# SCH_Pico_funboard_core2_2026-02-18.net
KiCad netlist of a schematic drawn in EasyEDA
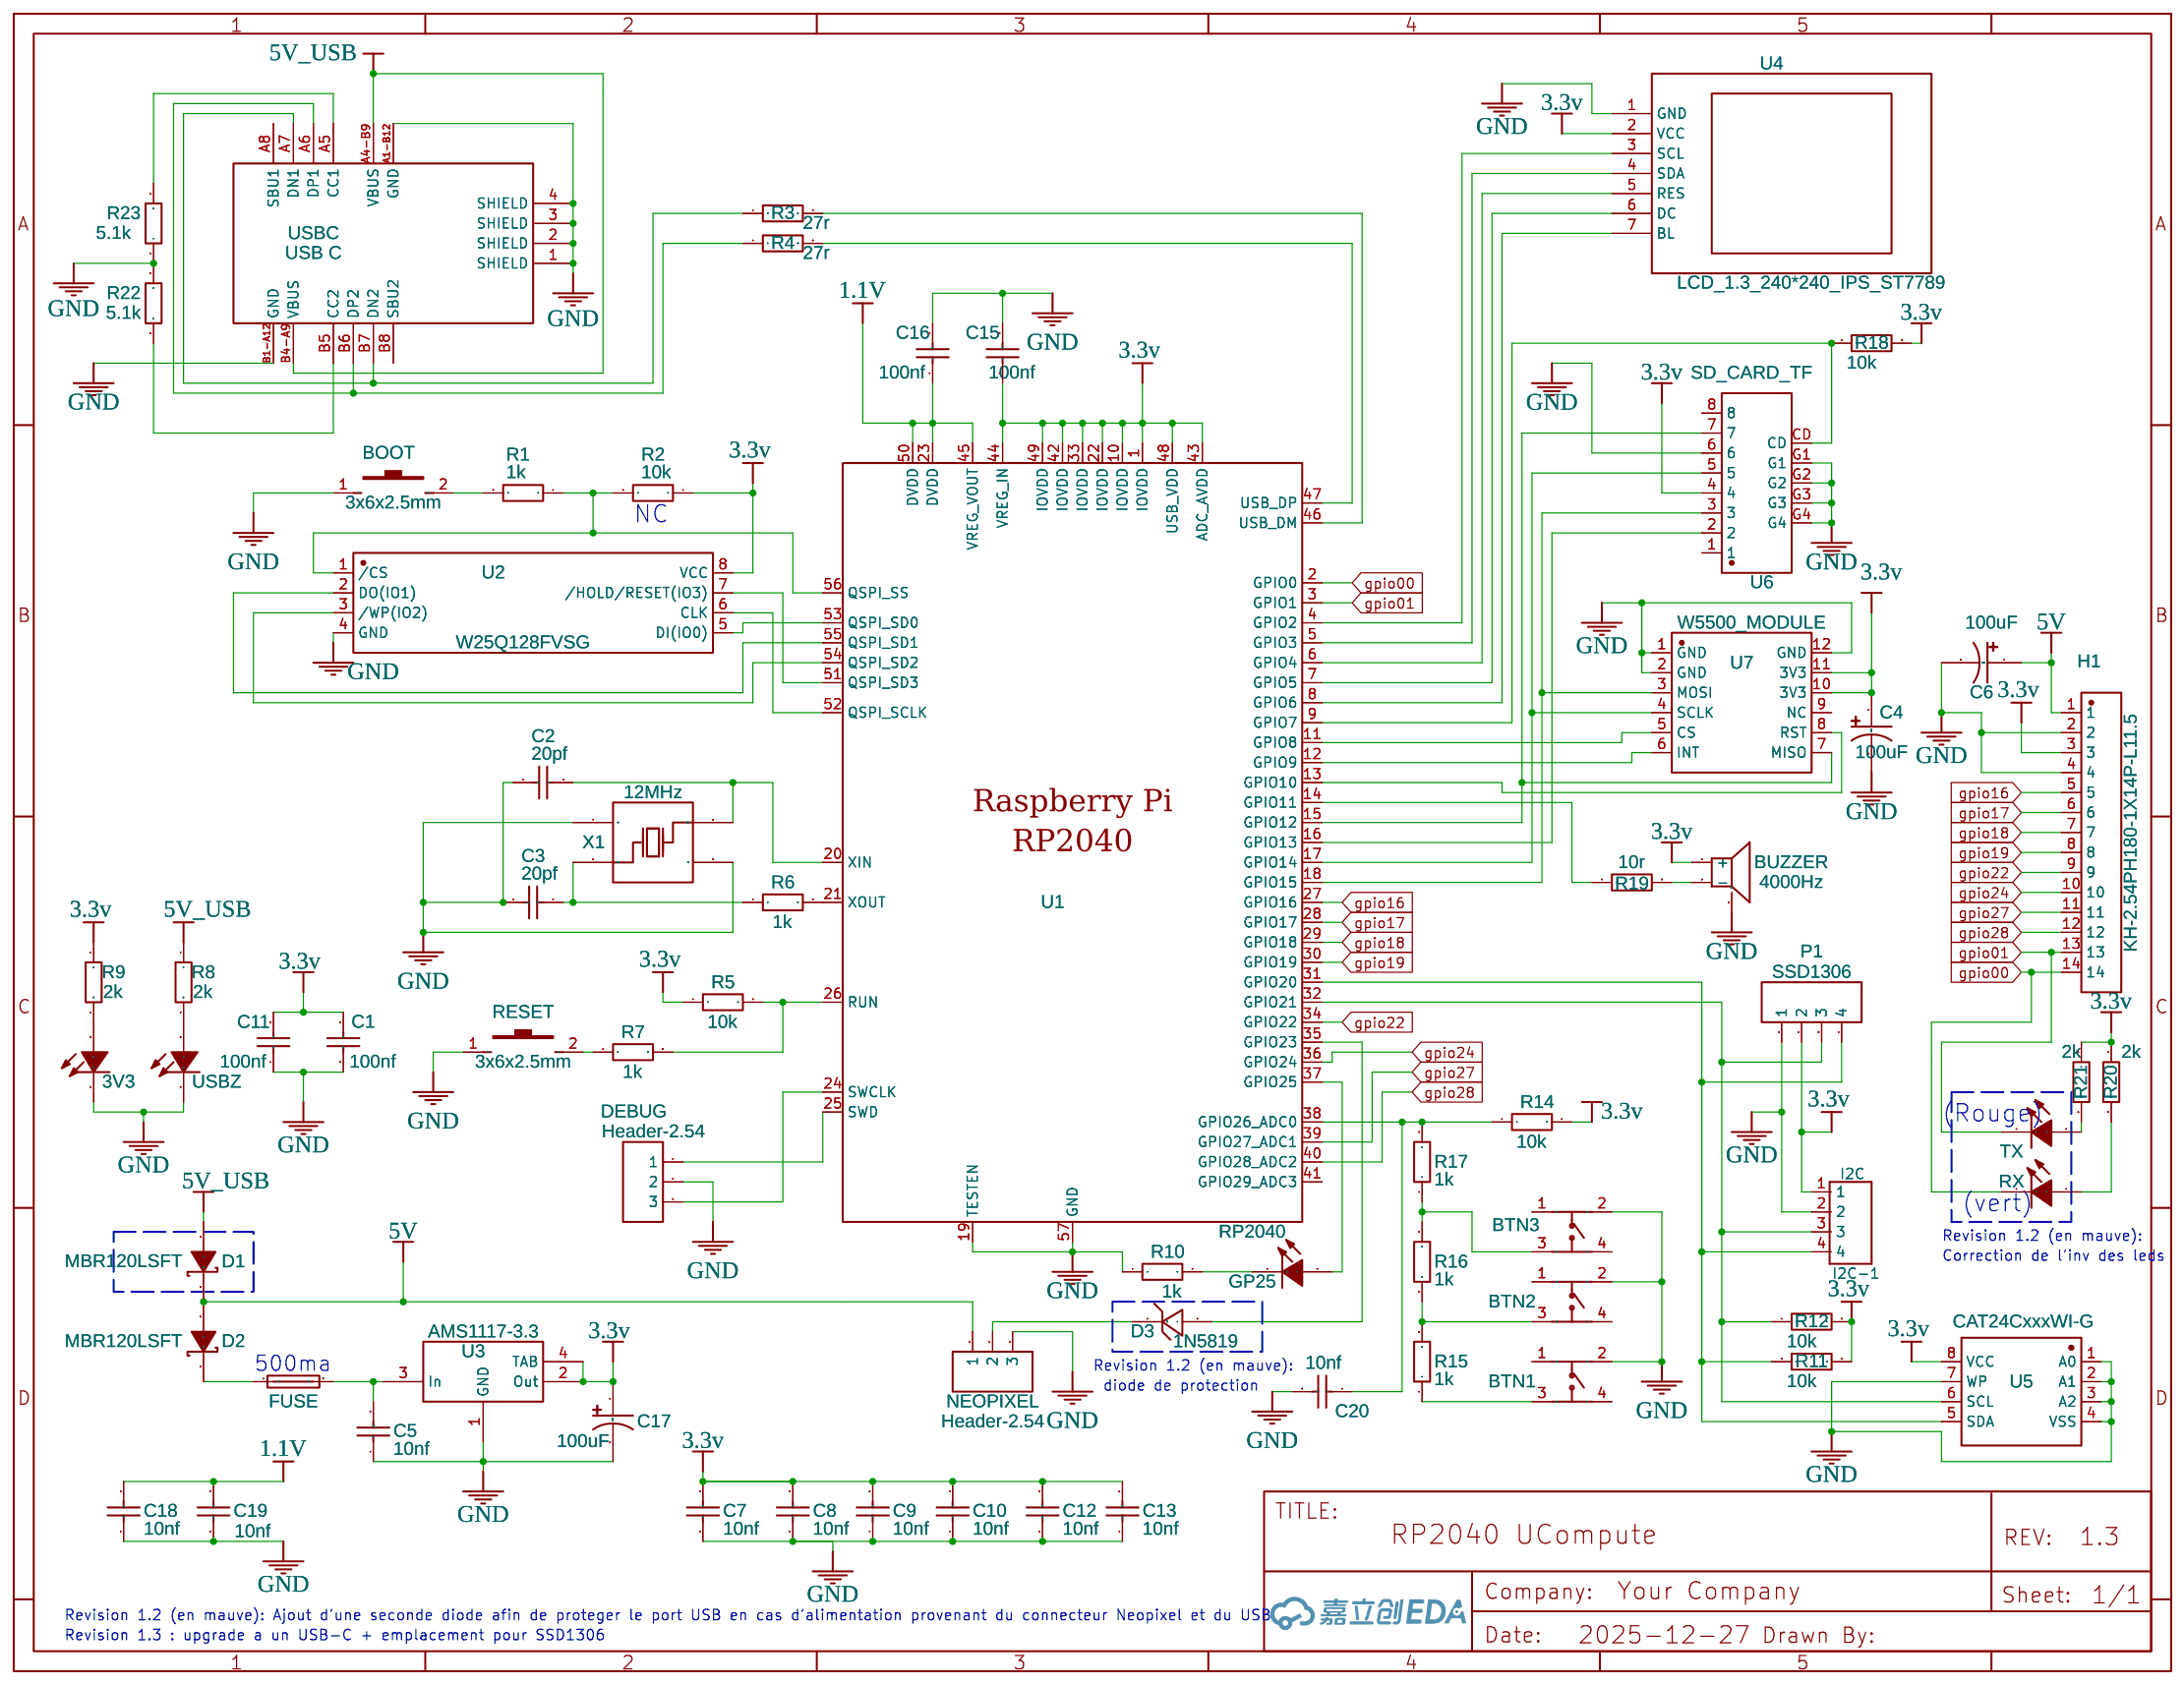
[diagram p0: schematic sheet]

(export (version "E")
  (design (tool "Eeschema 10.0.6"))
  (components
    (comp (ref "3V3")
      (value "XL-1206QPC")
      (fields (field (name "Manufacturer") "LCSC"))
      (libsource (lib "") (part "XL-1206QPC_4"))
    )
    (comp (ref "BOOT")
      (value "3x6x2.5mm")
      (fields (field (name "Manufacturer") "ReliaPro"))
      (libsource (lib "") (part "3x6x2.5mm"))
    )
    (comp (ref "BTN1")
      (value "TC-1102-A-J-R")
      (fields (field (name "Manufacturer") "XKB Connectivity(中国星坤)"))
      (libsource (lib "") (part "TC-1102-A-J-R"))
    )
    (comp (ref "BTN2")
      (value "TC-1102-A-J-R")
      (fields (field (name "Manufacturer") "XKB Connectivity(中国星坤)"))
      (libsource (lib "") (part "TC-1102-A-J-R"))
    )
    (comp (ref "BTN3")
      (value "TC-1102-A-J-R")
      (fields (field (name "Manufacturer") "XKB Connectivity(中国星坤)"))
      (libsource (lib "") (part "TC-1102-A-J-R"))
    )
    (comp (ref "BUZZER")
      (value "4000Hz")
      (fields (field (name "Manufacturer Part") "MLT-5030") (field (name "Manufacturer") "华能"))
      (libsource (lib "") (part "MLT-5030"))
    )
    (comp (ref "C1")
      (value "100nf")
      (fields (field (name "Manufacturer Part") "0805CG220J500NT") (field (name "Manufacturer") "FH"))
      (libsource (lib "") (part "0805CG220J500NT_3"))
    )
    (comp (ref "C2")
      (value "20pf")
      (fields (field (name "Manufacturer Part") "0805CG220J500NT") (field (name "Manufacturer") "FH"))
      (libsource (lib "") (part "0805CG220J500NT_1"))
    )
    (comp (ref "C3")
      (value "20pf")
      (fields (field (name "Manufacturer Part") "0805CG220J500NT") (field (name "Manufacturer") "FH"))
      (libsource (lib "") (part "0805CG220J500NT_1"))
    )
    (comp (ref "C4")
      (value "100uF")
      (fields
        (field (name "Manufacturer Part") "TLJA107M010R1400")
        (field (name "Manufacturer") "Kyocera AVX")
      )
      (libsource (lib "") (part "TLJA107M010R1400_1"))
    )
    (comp (ref "C5")
      (value "10nf")
      (fields (field (name "Manufacturer Part") "0805CG220J500NT") (field (name "Manufacturer") "FH"))
      (libsource (lib "") (part "0805CG220J500NT"))
    )
    (comp (ref "C6")
      (value "100uF")
      (fields
        (field (name "Manufacturer Part") "TLJA107M010R1400")
        (field (name "Manufacturer") "Kyocera AVX")
      )
      (libsource (lib "") (part "TLJA107M010R1400_2"))
    )
    (comp (ref "C7")
      (value "10nf")
      (fields (field (name "Manufacturer Part") "0805CG220J500NT") (field (name "Manufacturer") "FH"))
      (libsource (lib "") (part "0805CG220J500NT"))
    )
    (comp (ref "C8")
      (value "10nf")
      (fields (field (name "Manufacturer Part") "0805CG220J500NT") (field (name "Manufacturer") "FH"))
      (libsource (lib "") (part "0805CG220J500NT"))
    )
    (comp (ref "C9")
      (value "10nf")
      (fields (field (name "Manufacturer Part") "0805CG220J500NT") (field (name "Manufacturer") "FH"))
      (libsource (lib "") (part "0805CG220J500NT"))
    )
    (comp (ref "C10")
      (value "10nf")
      (fields (field (name "Manufacturer Part") "0805CG220J500NT") (field (name "Manufacturer") "FH"))
      (libsource (lib "") (part "0805CG220J500NT"))
    )
    (comp (ref "C11")
      (value "100nf")
      (fields (field (name "Manufacturer Part") "0805CG220J500NT") (field (name "Manufacturer") "FH"))
      (libsource (lib "") (part "0805CG220J500NT"))
    )
    (comp (ref "C12")
      (value "10nf")
      (fields (field (name "Manufacturer Part") "0805CG220J500NT") (field (name "Manufacturer") "FH"))
      (libsource (lib "") (part "0805CG220J500NT"))
    )
    (comp (ref "C13")
      (value "10nf")
      (fields (field (name "Manufacturer Part") "0805CG220J500NT") (field (name "Manufacturer") "FH"))
      (libsource (lib "") (part "0805CG220J500NT"))
    )
    (comp (ref "C15")
      (value "100nf")
      (fields (field (name "Manufacturer Part") "0805CG220J500NT") (field (name "Manufacturer") "FH"))
      (libsource (lib "") (part "0805CG220J500NT"))
    )
    (comp (ref "C16")
      (value "100nf")
      (fields (field (name "Manufacturer Part") "0805CG220J500NT") (field (name "Manufacturer") "FH"))
      (libsource (lib "") (part "0805CG220J500NT"))
    )
    (comp (ref "C17")
      (value "100uF")
      (fields
        (field (name "Manufacturer Part") "TLJA107M010R1400")
        (field (name "Manufacturer") "Kyocera AVX")
      )
      (libsource (lib "") (part "TLJA107M010R1400"))
    )
    (comp (ref "C18")
      (value "10nf")
      (fields (field (name "Manufacturer Part") "0805CG220J500NT") (field (name "Manufacturer") "FH"))
      (libsource (lib "") (part "0805CG220J500NT"))
    )
    (comp (ref "C19")
      (value "10nf")
      (fields (field (name "Manufacturer Part") "0805CG220J500NT") (field (name "Manufacturer") "FH"))
      (libsource (lib "") (part "0805CG220J500NT"))
    )
    (comp (ref "C20")
      (value "10nf")
      (fields (field (name "Manufacturer Part") "0805CG220J500NT") (field (name "Manufacturer") "FH"))
      (libsource (lib "") (part "0805CG220J500NT_2"))
    )
    (comp (ref "D1")
      (value "MBR120LSFT")
      (fields
        (field (name "Manufacturer Part") "SS110A")
        (field (name "Manufacturer") "Yangzhou Yangjie Elec Tech")
      )
      (libsource (lib "") (part "SS110A"))
    )
    (comp (ref "D2")
      (value "MBR120LSFT")
      (fields
        (field (name "Manufacturer Part") "SS110A")
        (field (name "Manufacturer") "Yangzhou Yangjie Elec Tech")
      )
      (libsource (lib "") (part "SS110A"))
    )
    (comp (ref "D3")
      (value "1N5819")
      (fields (field (name "Manufacturer Part") "1N4148D"))
      (libsource (lib "") (part "1N4148D"))
    )
    (comp (ref "DEBUG")
      (value "Header-2.54")
      (fields (field (name "Manufacturer Part") "2.54-1*3P针") (field (name "Manufacturer") "BOOMELE(博穆精密)"))
      (libsource (lib "") (part "Header-Male-2.54_1x3"))
    )
    (comp (ref "FUSE")
      (value "FUSE1206")
      (fields (field (name "Manufacturer Part") "D22051903536_fuse1206"))
      (libsource (lib "") (part "D22051903536_FUSE1206"))
    )
    (comp (ref "GP25")
      (value "XL-1206QPC")
      (fields (field (name "Manufacturer") "LCSC"))
      (libsource (lib "") (part "XL-1206QPC_3"))
    )
    (comp (ref "H1")
      (value "KH-2.54PH180-1X14P-L11.5")
      (fields (field (name "Manufacturer") "kinghelm(金航标)"))
      (libsource (lib "") (part "KH-2.54PH180-1X14P-L11.5"))
    )
    (comp (ref "I2C-1") (value "I2C") (libsource (lib "") (part "Unknown_921_-225")))
    (comp (ref "NEOPIXEL")
      (value "Header-2.54")
      (fields (field (name "Manufacturer Part") "2.54-1*3P针") (field (name "Manufacturer") "BOOMELE(博穆精密)"))
      (libsource (lib "") (part "Header-Male-2.54_1x3_1"))
    )
    (comp (ref "P1")
      (value "SSD1306")
      (fields
        (field (name "Manufacturer Part") "Header-Female-2.54_1x4")
        (field (name "Manufacturer") "ReliaPro")
      )
      (libsource (lib "") (part "Header-Female-2.54_1x4"))
    )
    (comp (ref "R1")
      (value "1k")
      (fields (field (name "Manufacturer Part") "RC0805DR-071KL") (field (name "Manufacturer") "YAGEO(国巨)"))
      (libsource (lib "") (part "RC0805DR-071KL_2"))
    )
    (comp (ref "R2")
      (value "10k")
      (fields (field (name "Manufacturer Part") "RC0805DR-071KL") (field (name "Manufacturer") "YAGEO(国巨)"))
      (libsource (lib "") (part "RC0805DR-071KL_2"))
    )
    (comp (ref "R3")
      (value "27r")
      (fields (field (name "Manufacturer Part") "RC0805DR-071KL") (field (name "Manufacturer") "YAGEO(国巨)"))
      (libsource (lib "") (part "RC0805DR-071KL_1"))
    )
    (comp (ref "R4")
      (value "27r")
      (fields (field (name "Manufacturer Part") "RC0805DR-071KL") (field (name "Manufacturer") "YAGEO(国巨)"))
      (libsource (lib "") (part "RC0805DR-071KL_1"))
    )
    (comp (ref "R5")
      (value "10k")
      (fields (field (name "Manufacturer Part") "RC0805DR-071KL") (field (name "Manufacturer") "YAGEO(国巨)"))
      (libsource (lib "") (part "RC0805DR-071KL_1"))
    )
    (comp (ref "R6")
      (value "1k")
      (fields (field (name "Manufacturer Part") "RC0805DR-071KL") (field (name "Manufacturer") "YAGEO(国巨)"))
      (libsource (lib "") (part "RC0805DR-071KL_1"))
    )
    (comp (ref "R7")
      (value "1k")
      (fields (field (name "Manufacturer Part") "RC0805DR-071KL") (field (name "Manufacturer") "YAGEO(国巨)"))
      (libsource (lib "") (part "RC0805DR-071KL_1"))
    )
    (comp (ref "R8")
      (value "2k")
      (fields (field (name "Manufacturer Part") "RC0805DR-071KL") (field (name "Manufacturer") "YAGEO(国巨)"))
      (libsource (lib "") (part "RC0805DR-071KL"))
    )
    (comp (ref "R9")
      (value "2k")
      (fields (field (name "Manufacturer Part") "RC0805DR-071KL") (field (name "Manufacturer") "YAGEO(国巨)"))
      (libsource (lib "") (part "RC0805DR-071KL"))
    )
    (comp (ref "R10")
      (value "1k")
      (fields (field (name "Manufacturer Part") "RC0805DR-071KL") (field (name "Manufacturer") "YAGEO(国巨)"))
      (libsource (lib "") (part "RC0805DR-071KL_1"))
    )
    (comp (ref "R11")
      (value "10k")
      (fields (field (name "Manufacturer Part") "RC0805DR-071KL") (field (name "Manufacturer") "YAGEO(国巨)"))
      (libsource (lib "") (part "RC0805DR-071KL_1"))
    )
    (comp (ref "R12")
      (value "10k")
      (fields (field (name "Manufacturer Part") "RC0805DR-071KL") (field (name "Manufacturer") "YAGEO(国巨)"))
      (libsource (lib "") (part "RC0805DR-071KL_1"))
    )
    (comp (ref "R14")
      (value "10k")
      (fields (field (name "Manufacturer Part") "RC0805DR-071KL") (field (name "Manufacturer") "YAGEO(国巨)"))
      (libsource (lib "") (part "RC0805DR-071KL_1"))
    )
    (comp (ref "R15")
      (value "1k")
      (fields (field (name "Manufacturer Part") "RC0805DR-071KL") (field (name "Manufacturer") "YAGEO(国巨)"))
      (libsource (lib "") (part "RC0805DR-071KL_3"))
    )
    (comp (ref "R16")
      (value "1k")
      (fields (field (name "Manufacturer Part") "RC0805DR-071KL") (field (name "Manufacturer") "YAGEO(国巨)"))
      (libsource (lib "") (part "RC0805DR-071KL_3"))
    )
    (comp (ref "R17")
      (value "1k")
      (fields (field (name "Manufacturer Part") "RC0805DR-071KL") (field (name "Manufacturer") "YAGEO(国巨)"))
      (libsource (lib "") (part "RC0805DR-071KL_3"))
    )
    (comp (ref "R18")
      (value "10k")
      (fields (field (name "Manufacturer Part") "RC0805DR-071KL") (field (name "Manufacturer") "YAGEO(国巨)"))
      (libsource (lib "") (part "RC0805DR-071KL_1"))
    )
    (comp (ref "R19")
      (value "10r")
      (fields (field (name "Manufacturer Part") "RC0805DR-071KL") (field (name "Manufacturer") "YAGEO(国巨)"))
      (libsource (lib "") (part "RC0805DR-071KL_1"))
    )
    (comp (ref "R20")
      (value "2k")
      (fields (field (name "Manufacturer Part") "RC0805DR-071KL") (field (name "Manufacturer") "YAGEO(国巨)"))
      (libsource (lib "") (part "RC0805DR-071KL"))
    )
    (comp (ref "R21")
      (value "2k")
      (fields (field (name "Manufacturer Part") "RC0805DR-071KL") (field (name "Manufacturer") "YAGEO(国巨)"))
      (libsource (lib "") (part "RC0805DR-071KL"))
    )
    (comp (ref "R22")
      (value "5.1k")
      (fields (field (name "Manufacturer Part") "RC0805DR-071KL") (field (name "Manufacturer") "YAGEO(国巨)"))
      (libsource (lib "") (part "RC0805DR-071KL_3"))
    )
    (comp (ref "R23")
      (value "5.1k")
      (fields (field (name "Manufacturer Part") "RC0805DR-071KL") (field (name "Manufacturer") "YAGEO(国巨)"))
      (libsource (lib "") (part "RC0805DR-071KL_3"))
    )
    (comp (ref "RESET")
      (value "3x6x2.5mm")
      (fields (field (name "Manufacturer") "ReliaPro"))
      (libsource (lib "") (part "3x6x2.5mm_1"))
    )
    (comp (ref "RX1")
      (value "RX")
      (fields (field (name "Manufacturer Part") "XL-1206QPC") (field (name "Manufacturer") "LCSC"))
      (libsource (lib "") (part "XL-1206QPC_1"))
    )
    (comp (ref "TX1")
      (value "TX")
      (fields (field (name "Manufacturer Part") "XL-1206QPC") (field (name "Manufacturer") "LCSC"))
      (libsource (lib "") (part "XL-1206QPC_2"))
    )
    (comp (ref "U1")
      (value "RP2040")
      (fields (field (name "Manufacturer") "Raspberry Pi(树莓派)"))
      (libsource (lib "") (part "RP2040"))
    )
    (comp (ref "U2") (value "W25Q128FVSG") (libsource (lib "") (part "W25Q128FVSG")))
    (comp (ref "U3")
      (value "AMS1117-3.3")
      (fields (field (name "Manufacturer Part") "AMS1117-5.0") (field (name "Manufacturer") "SK"))
      (libsource (lib "") (part "AMS1117-5.0_C165483"))
    )
    (comp (ref "U4")
      (value "LCD_1.3_240*240_IPS_ST7789")
      (libsource (lib "") (part "LCD_1.3_240*240_IPS_ST7789"))
    )
    (comp (ref "U5") (value "CAT24CxxxWI-G") (libsource (lib "") (part "CAT24C256WI-G")))
    (comp (ref "U6")
      (value "SD_CARD_TF")
      (fields (field (name "Manufacturer Part") "SD_Card_TF"))
      (libsource (lib "") (part "SD_CARD_TF"))
    )
    (comp (ref "U7") (value "W5500_MODULE") (libsource (lib "") (part "W5500_MODULE")))
    (comp (ref "USBC")
      (value "USB C")
      (fields (field (name "Manufacturer Part") "MC-311D") (field (name "Manufacturer") "SOFNG"))
      (libsource (lib "") (part "USB C"))
    )
    (comp (ref "USBZ")
      (value "XL-1206QPC")
      (fields (field (name "Manufacturer") "LCSC"))
      (libsource (lib "") (part "XL-1206QPC"))
    )
    (comp (ref "X1")
      (value "12MHz")
      (fields
        (field (name "Manufacturer Part") "TSX-3225 12MHz 20pF 30ppm")
        (field (name "Manufacturer") "EPSON")
      )
      (libsource (lib "") (part "TSX-3225 12MHz 20pF 30ppm"))
    )
  )
  (nets
    (net (code "1") (name "1.1V") (class "Default")
      (node (ref "C16") (pin "1") (pinfunction "1_1") (pintype "input"))
      (node (ref "C18") (pin "2") (pinfunction "2_2") (pintype "input"))
      (node (ref "C19") (pin "2") (pinfunction "2_2") (pintype "input"))
      (node (ref "U1") (pin "23") (pinfunction "DVDD_23") (pintype "bidirectional"))
      (node (ref "U1") (pin "45") (pinfunction "VREG_VOUT_45") (pintype "bidirectional"))
      (node (ref "U1") (pin "50") (pinfunction "DVDD_50") (pintype "bidirectional"))
    )
    (net (code "2") (name "3.3v") (class "Default")
      (node (ref "BUZZER") (pin "2") (pinfunction "+_2") (pintype "unspecified"))
      (node (ref "C1") (pin "1") (pinfunction "1_1") (pintype "input"))
      (node (ref "C10") (pin "2") (pinfunction "2_2") (pintype "input"))
      (node (ref "C11") (pin "2") (pinfunction "2_2") (pintype "input"))
      (node (ref "C12") (pin "2") (pinfunction "2_2") (pintype "input"))
      (node (ref "C13") (pin "2") (pinfunction "2_2") (pintype "input"))
      (node (ref "C15") (pin "1") (pinfunction "1_1") (pintype "input"))
      (node (ref "C17") (pin "1") (pinfunction "1_1") (pintype "unspecified"))
      (node (ref "C4") (pin "1") (pinfunction "1_1") (pintype "unspecified"))
      (node (ref "C7") (pin "2") (pinfunction "2_2") (pintype "input"))
      (node (ref "C8") (pin "2") (pinfunction "2_2") (pintype "input"))
      (node (ref "C9") (pin "2") (pinfunction "2_2") (pintype "input"))
      (node (ref "H1") (pin "3") (pinfunction "3_3") (pintype "unspecified"))
      (node (ref "I2C-1") (pin "1") (pinfunction "1_1") (pintype "bidirectional"))
      (node (ref "P1") (pin "2") (pinfunction "2_2") (pintype "input"))
      (node (ref "R11") (pin "2") (pinfunction "2_2") (pintype "unspecified"))
      (node (ref "R12") (pin "2") (pinfunction "2_2") (pintype "unspecified"))
      (node (ref "R14") (pin "2") (pinfunction "2_2") (pintype "unspecified"))
      (node (ref "R18") (pin "2") (pinfunction "2_2") (pintype "unspecified"))
      (node (ref "R2") (pin "1") (pinfunction "1_1") (pintype "unspecified"))
      (node (ref "R20") (pin "1") (pinfunction "1_1") (pintype "unspecified"))
      (node (ref "R21") (pin "1") (pinfunction "1_1") (pintype "unspecified"))
      (node (ref "R5") (pin "1") (pinfunction "1_1") (pintype "unspecified"))
      (node (ref "R9") (pin "1") (pinfunction "1_1") (pintype "unspecified"))
      (node (ref "U1") (pin "1") (pinfunction "IOVDD_1") (pintype "bidirectional"))
      (node (ref "U1") (pin "10") (pinfunction "IOVDD_10") (pintype "bidirectional"))
      (node (ref "U1") (pin "22") (pinfunction "IOVDD_22") (pintype "bidirectional"))
      (node (ref "U1") (pin "33") (pinfunction "IOVDD_33") (pintype "bidirectional"))
      (node (ref "U1") (pin "42") (pinfunction "IOVDD_42") (pintype "bidirectional"))
      (node (ref "U1") (pin "43") (pinfunction "ADC_AVDD_43") (pintype "bidirectional"))
      (node (ref "U1") (pin "44") (pinfunction "VREG_IN_44") (pintype "bidirectional"))
      (node (ref "U1") (pin "48") (pinfunction "USB_VDD_48") (pintype "bidirectional"))
      (node (ref "U1") (pin "49") (pinfunction "IOVDD_49") (pintype "bidirectional"))
      (node (ref "U2") (pin "8") (pinfunction "VCC_8") (pintype "unspecified"))
      (node (ref "U3") (pin "2") (pinfunction "Out_2") (pintype "unspecified"))
      (node (ref "U3") (pin "4") (pinfunction "TAB_4") (pintype "unspecified"))
      (node (ref "U4") (pin "2") (pinfunction "VCC_2") (pintype "unspecified"))
      (node (ref "U5") (pin "8") (pinfunction "VCC_8") (pintype "unspecified"))
      (node (ref "U6") (pin "4") (pinfunction "4_4") (pintype "unspecified"))
      (node (ref "U7") (pin "10") (pinfunction "3V3_10") (pintype "unspecified"))
      (node (ref "U7") (pin "11") (pinfunction "3V3_11") (pintype "unspecified"))
    )
    (net (code "3") (name "5V") (class "Default")
      (node (ref "C6") (pin "1") (pinfunction "1_1") (pintype "unspecified"))
      (node (ref "D1") (pin "2") (pinfunction "A_2") (pintype "unspecified"))
      (node (ref "D2") (pin "1") (pinfunction "K_1") (pintype "unspecified"))
      (node (ref "H1") (pin "1") (pinfunction "1_1") (pintype "unspecified"))
      (node (ref "NEOPIXEL") (pin "1") (pinfunction "1_1") (pintype "input"))
    )
    (net (code "4") (name "5V_USB") (class "Default")
      (node (ref "D2") (pin "2") (pinfunction "A_2") (pintype "unspecified"))
      (node (ref "R8") (pin "1") (pinfunction "1_1") (pintype "unspecified"))
      (node (ref "USBC") (pin "A4-B9") (pinfunction "VBUS_A4-B9") (pintype "unspecified"))
      (node (ref "USBC") (pin "B4-A9") (pinfunction "VBUS_B4-A9") (pintype "unspecified"))
    )
    (net (code "5") (name "GND") (class "Default")
      (node (ref "3V3") (pin "1") (pinfunction "K_1") (pintype "unspecified"))
      (node (ref "BOOT") (pin "1") (pinfunction "1_1") (pintype "input"))
      (node (ref "BTN1") (pin "2") (pinfunction "2_2") (pintype "unspecified"))
      (node (ref "BTN2") (pin "2") (pinfunction "2_2") (pintype "unspecified"))
      (node (ref "BTN3") (pin "2") (pinfunction "2_2") (pintype "unspecified"))
      (node (ref "BUZZER") (pin "1") (pinfunction "NC_1") (pintype "unspecified"))
      (node (ref "C1") (pin "2") (pinfunction "2_2") (pintype "input"))
      (node (ref "C10") (pin "1") (pinfunction "1_1") (pintype "input"))
      (node (ref "C11") (pin "1") (pinfunction "1_1") (pintype "input"))
      (node (ref "C12") (pin "1") (pinfunction "1_1") (pintype "input"))
      (node (ref "C13") (pin "1") (pinfunction "1_1") (pintype "input"))
      (node (ref "C15") (pin "2") (pinfunction "2_2") (pintype "input"))
      (node (ref "C16") (pin "2") (pinfunction "2_2") (pintype "input"))
      (node (ref "C17") (pin "2") (pinfunction "2_2") (pintype "unspecified"))
      (node (ref "C18") (pin "1") (pinfunction "1_1") (pintype "input"))
      (node (ref "C19") (pin "1") (pinfunction "1_1") (pintype "input"))
      (node (ref "C2") (pin "1") (pinfunction "1_1") (pintype "input"))
      (node (ref "C20") (pin "2") (pinfunction "2_2") (pintype "input"))
      (node (ref "C3") (pin "1") (pinfunction "1_1") (pintype "input"))
      (node (ref "C4") (pin "2") (pinfunction "2_2") (pintype "unspecified"))
      (node (ref "C5") (pin "1") (pinfunction "1_1") (pintype "input"))
      (node (ref "C6") (pin "2") (pinfunction "2_2") (pintype "unspecified"))
      (node (ref "C7") (pin "1") (pinfunction "1_1") (pintype "input"))
      (node (ref "C8") (pin "1") (pinfunction "1_1") (pintype "input"))
      (node (ref "C9") (pin "1") (pinfunction "1_1") (pintype "input"))
      (node (ref "DEBUG") (pin "2") (pinfunction "2_2") (pintype "input"))
      (node (ref "H1") (pin "2") (pinfunction "2_2") (pintype "unspecified"))
      (node (ref "H1") (pin "4") (pinfunction "4_4") (pintype "unspecified"))
      (node (ref "I2C-1") (pin "2") (pinfunction "2_2") (pintype "bidirectional"))
      (node (ref "NEOPIXEL") (pin "3") (pinfunction "3_3") (pintype "input"))
      (node (ref "P1") (pin "1") (pinfunction "1_1") (pintype "input"))
      (node (ref "R10") (pin "1") (pinfunction "1_1") (pintype "unspecified"))
      (node (ref "R22") (pin "2") (pinfunction "2_2") (pintype "unspecified"))
      (node (ref "R23") (pin "1") (pinfunction "1_1") (pintype "unspecified"))
      (node (ref "RESET") (pin "1") (pinfunction "1_1") (pintype "input"))
      (node (ref "U1") (pin "19") (pinfunction "TESTEN_19") (pintype "unspecified"))
      (node (ref "U1") (pin "57") (pinfunction "GND_57") (pintype "bidirectional"))
      (node (ref "U2") (pin "4") (pinfunction "GND_4") (pintype "unspecified"))
      (node (ref "U3") (pin "1") (pinfunction "GND_1") (pintype "unspecified"))
      (node (ref "U4") (pin "1") (pinfunction "GND_1") (pintype "unspecified"))
      (node (ref "U5") (pin "1") (pinfunction "A0_1") (pintype "unspecified"))
      (node (ref "U5") (pin "2") (pinfunction "A1_2") (pintype "unspecified"))
      (node (ref "U5") (pin "3") (pinfunction "A2_3") (pintype "unspecified"))
      (node (ref "U5") (pin "4") (pinfunction "VSS_4") (pintype "unspecified"))
      (node (ref "U5") (pin "7") (pinfunction "WP_7") (pintype "unspecified"))
      (node (ref "U6") (pin "6") (pinfunction "6_6") (pintype "unspecified"))
      (node (ref "U6") (pin "G1") (pinfunction "G1_G1") (pintype "unspecified"))
      (node (ref "U6") (pin "G2") (pinfunction "G2_G2") (pintype "unspecified"))
      (node (ref "U6") (pin "G3") (pinfunction "G3_G3") (pintype "unspecified"))
      (node (ref "U6") (pin "G4") (pinfunction "G4_G4") (pintype "unspecified"))
      (node (ref "U7") (pin "1") (pinfunction "GND_1") (pintype "unspecified"))
      (node (ref "U7") (pin "12") (pinfunction "GND_12") (pintype "unspecified"))
      (node (ref "U7") (pin "2") (pinfunction "GND_2") (pintype "unspecified"))
      (node (ref "USBC") (pin "1") (pinfunction "SHIELD_1") (pintype "unspecified"))
      (node (ref "USBC") (pin "2") (pinfunction "SHIELD_2") (pintype "unspecified"))
      (node (ref "USBC") (pin "3") (pinfunction "SHIELD_3") (pintype "unspecified"))
      (node (ref "USBC") (pin "4") (pinfunction "SHIELD_4") (pintype "unspecified"))
      (node (ref "USBC") (pin "A1-B12") (pinfunction "GND_A1-B12") (pintype "unspecified"))
      (node (ref "USBC") (pin "B1-A12") (pinfunction "GND_B1-A12") (pintype "unspecified"))
      (node (ref "USBZ") (pin "1") (pinfunction "K_1") (pintype "unspecified"))
      (node (ref "X1") (pin "2") (pinfunction "NC_2") (pintype "input"))
      (node (ref "X1") (pin "4") (pinfunction "NC_4") (pintype "input"))
    )
    (net (code "6") (name "Net-(3V3-A)") (class "Default")
      (node (ref "3V3") (pin "2") (pinfunction "A_2") (pintype "unspecified"))
      (node (ref "R9") (pin "2") (pinfunction "2_2") (pintype "unspecified"))
    )
    (net (code "7") (name "Net-(BOOT-Pad2)") (class "Default")
      (node (ref "BOOT") (pin "2") (pinfunction "2_2") (pintype "input"))
      (node (ref "R1") (pin "2") (pinfunction "2_2") (pintype "unspecified"))
    )
    (net (code "8") (name "Net-(BTN1-Pad3)") (class "Default")
      (node (ref "BTN1") (pin "3") (pinfunction "3_3") (pintype "unspecified"))
      (node (ref "R15") (pin "1") (pinfunction "1_1") (pintype "unspecified"))
    )
    (net (code "9") (name "Net-(BTN2-Pad3)") (class "Default")
      (node (ref "BTN2") (pin "3") (pinfunction "3_3") (pintype "unspecified"))
      (node (ref "R15") (pin "2") (pinfunction "2_2") (pintype "unspecified"))
      (node (ref "R16") (pin "1") (pinfunction "1_1") (pintype "unspecified"))
    )
    (net (code "10") (name "Net-(BTN3-Pad3)") (class "Default")
      (node (ref "BTN3") (pin "3") (pinfunction "3_3") (pintype "unspecified"))
      (node (ref "R16") (pin "2") (pinfunction "2_2") (pintype "unspecified"))
      (node (ref "R17") (pin "1") (pinfunction "1_1") (pintype "unspecified"))
    )
    (net (code "11") (name "Net-(BUZZER--)") (class "Default")
      (node (ref "BUZZER") (pin "3") (pinfunction "-_3") (pintype "unspecified"))
      (node (ref "R19") (pin "2") (pinfunction "2_2") (pintype "unspecified"))
    )
    (net (code "12") (name "Net-(D1-K)") (class "Default")
      (node (ref "D1") (pin "1") (pinfunction "K_1") (pintype "unspecified"))
      (node (ref "FUSE") (pin "1") (pinfunction "1_1") (pintype "unspecified"))
    )
    (net (code "13") (name "Net-(D3-A)") (class "Default")
      (node (ref "D3") (pin "2") (pinfunction "A_2") (pintype "unspecified"))
      (node (ref "U1") (pin "35") (pinfunction "GPIO23_35") (pintype "bidirectional"))
    )
    (net (code "14") (name "Net-(D3-C)") (class "Default")
      (node (ref "D3") (pin "1") (pinfunction "C_1") (pintype "unspecified"))
      (node (ref "NEOPIXEL") (pin "2") (pinfunction "2_2") (pintype "input"))
    )
    (net (code "15") (name "Net-(GP25-A)") (class "Default")
      (node (ref "GP25") (pin "2") (pinfunction "A_2") (pintype "unspecified"))
      (node (ref "U1") (pin "37") (pinfunction "GPIO25_37") (pintype "bidirectional"))
    )
    (net (code "16") (name "Net-(GP25-K)") (class "Default")
      (node (ref "GP25") (pin "1") (pinfunction "K_1") (pintype "unspecified"))
      (node (ref "R10") (pin "2") (pinfunction "2_2") (pintype "unspecified"))
    )
    (net (code "17") (name "Net-(R7-Pad1)") (class "Default")
      (node (ref "R7") (pin "1") (pinfunction "1_1") (pintype "unspecified"))
      (node (ref "RESET") (pin "2") (pinfunction "2_2") (pintype "input"))
    )
    (net (code "18") (name "Net-(RX1-A)") (class "Default")
      (node (ref "R20") (pin "2") (pinfunction "2_2") (pintype "unspecified"))
      (node (ref "RX1") (pin "2") (pinfunction "A_2") (pintype "unspecified"))
    )
    (net (code "19") (name "Net-(TX1-A)") (class "Default")
      (node (ref "R21") (pin "2") (pinfunction "2_2") (pintype "unspecified"))
      (node (ref "TX1") (pin "2") (pinfunction "A_2") (pintype "unspecified"))
    )
    (net (code "20") (name "Net-(U1-GPIO2)") (class "Default")
      (node (ref "U1") (pin "4") (pinfunction "GPIO2_4") (pintype "bidirectional"))
      (node (ref "U4") (pin "3") (pinfunction "SCL_3") (pintype "unspecified"))
    )
    (net (code "21") (name "Net-(U1-GPIO3)") (class "Default")
      (node (ref "U1") (pin "5") (pinfunction "GPIO3_5") (pintype "bidirectional"))
      (node (ref "U4") (pin "4") (pinfunction "SDA_4") (pintype "unspecified"))
    )
    (net (code "22") (name "Net-(U1-GPIO4)") (class "Default")
      (node (ref "U1") (pin "6") (pinfunction "GPIO4_6") (pintype "bidirectional"))
      (node (ref "U4") (pin "5") (pinfunction "RES_5") (pintype "unspecified"))
    )
    (net (code "23") (name "Net-(U1-GPIO5)") (class "Default")
      (node (ref "U1") (pin "7") (pinfunction "GPIO5_7") (pintype "bidirectional"))
      (node (ref "U4") (pin "6") (pinfunction "DC_6") (pintype "unspecified"))
    )
    (net (code "24") (name "Net-(U1-GPIO6)") (class "Default")
      (node (ref "U1") (pin "8") (pinfunction "GPIO6_8") (pintype "bidirectional"))
      (node (ref "U4") (pin "7") (pinfunction "BL_7") (pintype "unspecified"))
    )
    (net (code "25") (name "Net-(U1-GPIO7)") (class "Default")
      (node (ref "R18") (pin "1") (pinfunction "1_1") (pintype "unspecified"))
      (node (ref "U1") (pin "9") (pinfunction "GPIO7_9") (pintype "bidirectional"))
      (node (ref "U6") (pin "CD") (pinfunction "CD_CD") (pintype "unspecified"))
    )
    (net (code "26") (name "Net-(U1-GPIO8)") (class "Default")
      (node (ref "U1") (pin "11") (pinfunction "GPIO8_11") (pintype "bidirectional"))
      (node (ref "U7") (pin "5") (pinfunction "CS_5") (pintype "unspecified"))
    )
    (net (code "27") (name "Net-(U1-GPIO9)") (class "Default")
      (node (ref "U1") (pin "12") (pinfunction "GPIO9_12") (pintype "bidirectional"))
      (node (ref "U7") (pin "6") (pinfunction "INT_6") (pintype "unspecified"))
    )
    (net (code "28") (name "Net-(U1-GPIO10)") (class "Default")
      (node (ref "U1") (pin "13") (pinfunction "GPIO10_13") (pintype "bidirectional"))
      (node (ref "U7") (pin "8") (pinfunction "RST_8") (pintype "unspecified"))
    )
    (net (code "29") (name "Net-(U1-GPIO11)") (class "Default")
      (node (ref "R19") (pin "1") (pinfunction "1_1") (pintype "unspecified"))
      (node (ref "U1") (pin "14") (pinfunction "GPIO11_14") (pintype "bidirectional"))
    )
    (net (code "30") (name "Net-(U1-GPIO12)") (class "Default")
      (node (ref "U1") (pin "15") (pinfunction "GPIO12_15") (pintype "bidirectional"))
      (node (ref "U6") (pin "7") (pinfunction "7_7") (pintype "unspecified"))
      (node (ref "U7") (pin "7") (pinfunction "MISO_7") (pintype "unspecified"))
    )
    (net (code "31") (name "Net-(U1-GPIO13)") (class "Default")
      (node (ref "U1") (pin "16") (pinfunction "GPIO13_16") (pintype "bidirectional"))
      (node (ref "U6") (pin "2") (pinfunction "2_2") (pintype "unspecified"))
    )
    (net (code "32") (name "Net-(U1-GPIO14)") (class "Default")
      (node (ref "U1") (pin "17") (pinfunction "GPIO14_17") (pintype "bidirectional"))
      (node (ref "U6") (pin "5") (pinfunction "5_5") (pintype "unspecified"))
      (node (ref "U7") (pin "4") (pinfunction "SCLK_4") (pintype "unspecified"))
    )
    (net (code "33") (name "Net-(U1-GPIO15)") (class "Default")
      (node (ref "U1") (pin "18") (pinfunction "GPIO15_18") (pintype "bidirectional"))
      (node (ref "U6") (pin "3") (pinfunction "3_3") (pintype "unspecified"))
      (node (ref "U7") (pin "3") (pinfunction "MOSI_3") (pintype "unspecified"))
    )
    (net (code "34") (name "Net-(U1-GPIO20)") (class "Default")
      (node (ref "I2C-1") (pin "4") (pinfunction "4_4") (pintype "bidirectional"))
      (node (ref "P1") (pin "4") (pinfunction "4_4") (pintype "input"))
      (node (ref "R11") (pin "1") (pinfunction "1_1") (pintype "unspecified"))
      (node (ref "U1") (pin "31") (pinfunction "GPIO20_31") (pintype "bidirectional"))
      (node (ref "U5") (pin "5") (pinfunction "SDA_5") (pintype "unspecified"))
    )
    (net (code "35") (name "Net-(U1-GPIO21)") (class "Default")
      (node (ref "I2C-1") (pin "3") (pinfunction "3_3") (pintype "bidirectional"))
      (node (ref "P1") (pin "3") (pinfunction "3_3") (pintype "input"))
      (node (ref "R12") (pin "1") (pinfunction "1_1") (pintype "unspecified"))
      (node (ref "U1") (pin "32") (pinfunction "GPIO21_32") (pintype "bidirectional"))
      (node (ref "U5") (pin "6") (pinfunction "SCL_6") (pintype "unspecified"))
    )
    (net (code "36") (name "Net-(U1-GPIO26_ADC0)") (class "Default")
      (node (ref "C20") (pin "1") (pinfunction "1_1") (pintype "input"))
      (node (ref "R14") (pin "1") (pinfunction "1_1") (pintype "unspecified"))
      (node (ref "R17") (pin "2") (pinfunction "2_2") (pintype "unspecified"))
      (node (ref "U1") (pin "38") (pinfunction "GPIO26_ADC0_38") (pintype "bidirectional"))
    )
    (net (code "37") (name "Net-(U1-QSPI_SCLK)") (class "Default")
      (node (ref "U1") (pin "52") (pinfunction "QSPI_SCLK_52") (pintype "output"))
      (node (ref "U2") (pin "6") (pinfunction "CLK_6") (pintype "unspecified"))
    )
    (net (code "38") (name "Net-(U1-QSPI_SD0)") (class "Default")
      (node (ref "U1") (pin "53") (pinfunction "QSPI_SD0_53") (pintype "bidirectional"))
      (node (ref "U2") (pin "5") (pinfunction "DI(IO0)_5") (pintype "unspecified"))
    )
    (net (code "39") (name "Net-(U1-QSPI_SD1)") (class "Default")
      (node (ref "U1") (pin "55") (pinfunction "QSPI_SD1_55") (pintype "bidirectional"))
      (node (ref "U2") (pin "2") (pinfunction "DO(IO1)_2") (pintype "unspecified"))
    )
    (net (code "40") (name "Net-(U1-QSPI_SD2)") (class "Default")
      (node (ref "U1") (pin "54") (pinfunction "QSPI_SD2_54") (pintype "bidirectional"))
      (node (ref "U2") (pin "3") (pinfunction "/WP(IO2)_3") (pintype "unspecified"))
    )
    (net (code "41") (name "Net-(U1-QSPI_SD3)") (class "Default")
      (node (ref "U1") (pin "51") (pinfunction "QSPI_SD3_51") (pintype "bidirectional"))
      (node (ref "U2") (pin "7") (pinfunction "/HOLD/RESET(IO3)_7") (pintype "unspecified"))
    )
    (net (code "42") (name "Net-(U1-QSPI_SS)") (class "Default")
      (node (ref "R1") (pin "1") (pinfunction "1_1") (pintype "unspecified"))
      (node (ref "R2") (pin "2") (pinfunction "2_2") (pintype "unspecified"))
      (node (ref "U1") (pin "56") (pinfunction "QSPI_SS_56") (pintype "bidirectional"))
      (node (ref "U2") (pin "1") (pinfunction "/CS_1") (pintype "unspecified"))
    )
    (net (code "43") (name "Net-(U1-RUN)") (class "Default")
      (node (ref "R5") (pin "2") (pinfunction "2_2") (pintype "unspecified"))
      (node (ref "R7") (pin "2") (pinfunction "2_2") (pintype "unspecified"))
      (node (ref "U1") (pin "26") (pinfunction "RUN_26") (pintype "input"))
    )
    (net (code "44") (name "Net-(U1-SWCLK)") (class "Default")
      (node (ref "DEBUG") (pin "3") (pinfunction "3_3") (pintype "input"))
      (node (ref "U1") (pin "24") (pinfunction "SWCLK_24") (pintype "output"))
    )
    (net (code "45") (name "Net-(U1-SWD)") (class "Default")
      (node (ref "DEBUG") (pin "1") (pinfunction "1_1") (pintype "input"))
      (node (ref "U1") (pin "25") (pinfunction "SWD_25") (pintype "bidirectional"))
    )
    (net (code "46") (name "Net-(U1-USB_DM)") (class "Default")
      (node (ref "R3") (pin "2") (pinfunction "2_2") (pintype "unspecified"))
      (node (ref "U1") (pin "46") (pinfunction "USB_DM_46") (pintype "bidirectional"))
    )
    (net (code "47") (name "Net-(U1-USB_DP)") (class "Default")
      (node (ref "R4") (pin "2") (pinfunction "2_2") (pintype "unspecified"))
      (node (ref "U1") (pin "47") (pinfunction "USB_DP_47") (pintype "bidirectional"))
    )
    (net (code "48") (name "Net-(U1-XIN)") (class "Default")
      (node (ref "C2") (pin "2") (pinfunction "2_2") (pintype "input"))
      (node (ref "U1") (pin "20") (pinfunction "XIN_20") (pintype "input"))
      (node (ref "X1") (pin "3") (pinfunction "OSC2_3") (pintype "input"))
    )
    (net (code "49") (name "Net-(U1-XOUT)") (class "Default")
      (node (ref "R6") (pin "2") (pinfunction "2_2") (pintype "unspecified"))
      (node (ref "U1") (pin "21") (pinfunction "XOUT_21") (pintype "unspecified"))
    )
    (net (code "50") (name "Net-(U3-In)") (class "Default")
      (node (ref "C5") (pin "2") (pinfunction "2_2") (pintype "input"))
      (node (ref "FUSE") (pin "2") (pinfunction "2_2") (pintype "unspecified"))
      (node (ref "U3") (pin "3") (pinfunction "In_3") (pintype "unspecified"))
    )
    (net (code "51") (name "Net-(USBC-CC1)") (class "Default")
      (node (ref "R23") (pin "2") (pinfunction "2_2") (pintype "unspecified"))
      (node (ref "USBC") (pin "A5") (pinfunction "CC1_A5") (pintype "unspecified"))
    )
    (net (code "52") (name "Net-(USBC-CC2)") (class "Default")
      (node (ref "R22") (pin "1") (pinfunction "1_1") (pintype "unspecified"))
      (node (ref "USBC") (pin "B5") (pinfunction "CC2_B5") (pintype "unspecified"))
    )
    (net (code "53") (name "Net-(USBC-DN1)") (class "Default")
      (node (ref "R3") (pin "1") (pinfunction "1_1") (pintype "unspecified"))
      (node (ref "USBC") (pin "A7") (pinfunction "DN1_A7") (pintype "unspecified"))
      (node (ref "USBC") (pin "B7") (pinfunction "DN2_B7") (pintype "unspecified"))
    )
    (net (code "54") (name "Net-(USBC-DP1)") (class "Default")
      (node (ref "R4") (pin "1") (pinfunction "1_1") (pintype "unspecified"))
      (node (ref "USBC") (pin "A6") (pinfunction "DP1_A6") (pintype "unspecified"))
      (node (ref "USBC") (pin "B6") (pinfunction "DP2_B6") (pintype "unspecified"))
    )
    (net (code "55") (name "Net-(USBZ-A)") (class "Default")
      (node (ref "R8") (pin "2") (pinfunction "2_2") (pintype "unspecified"))
      (node (ref "USBZ") (pin "2") (pinfunction "A_2") (pintype "unspecified"))
    )
    (net (code "56") (name "Net-(X1-OSC1)") (class "Default")
      (node (ref "C3") (pin "2") (pinfunction "2_2") (pintype "input"))
      (node (ref "R6") (pin "1") (pinfunction "1_1") (pintype "unspecified"))
      (node (ref "X1") (pin "1") (pinfunction "OSC1_1") (pintype "input"))
    )
    (net (code "57") (name "gpio00") (class "Default")
      (node (ref "H1") (pin "14") (pinfunction "14_14") (pintype "unspecified"))
      (node (ref "RX1") (pin "1") (pinfunction "K_1") (pintype "unspecified"))
      (node (ref "U1") (pin "2") (pinfunction "GPIO0_2") (pintype "bidirectional"))
    )
    (net (code "58") (name "gpio01") (class "Default")
      (node (ref "H1") (pin "13") (pinfunction "13_13") (pintype "unspecified"))
      (node (ref "TX1") (pin "1") (pinfunction "K_1") (pintype "unspecified"))
      (node (ref "U1") (pin "3") (pinfunction "GPIO1_3") (pintype "bidirectional"))
    )
    (net (code "59") (name "gpio16") (class "Default")
      (node (ref "H1") (pin "5") (pinfunction "5_5") (pintype "unspecified"))
      (node (ref "U1") (pin "27") (pinfunction "GPIO16_27") (pintype "bidirectional"))
    )
    (net (code "60") (name "gpio17") (class "Default")
      (node (ref "H1") (pin "6") (pinfunction "6_6") (pintype "unspecified"))
      (node (ref "U1") (pin "28") (pinfunction "GPIO17_28") (pintype "bidirectional"))
    )
    (net (code "61") (name "gpio18") (class "Default")
      (node (ref "H1") (pin "7") (pinfunction "7_7") (pintype "unspecified"))
      (node (ref "U1") (pin "29") (pinfunction "GPIO18_29") (pintype "bidirectional"))
    )
    (net (code "62") (name "gpio19") (class "Default")
      (node (ref "H1") (pin "8") (pinfunction "8_8") (pintype "unspecified"))
      (node (ref "U1") (pin "30") (pinfunction "GPIO19_30") (pintype "bidirectional"))
    )
    (net (code "63") (name "gpio22") (class "Default")
      (node (ref "H1") (pin "9") (pinfunction "9_9") (pintype "unspecified"))
      (node (ref "U1") (pin "34") (pinfunction "GPIO22_34") (pintype "bidirectional"))
    )
    (net (code "64") (name "gpio24") (class "Default")
      (node (ref "H1") (pin "10") (pinfunction "10_10") (pintype "unspecified"))
      (node (ref "U1") (pin "36") (pinfunction "GPIO24_36") (pintype "bidirectional"))
    )
    (net (code "65") (name "gpio27") (class "Default")
      (node (ref "H1") (pin "11") (pinfunction "11_11") (pintype "unspecified"))
      (node (ref "U1") (pin "39") (pinfunction "GPIO27_ADC1_39") (pintype "bidirectional"))
    )
    (net (code "66") (name "gpio28") (class "Default")
      (node (ref "H1") (pin "12") (pinfunction "12_12") (pintype "unspecified"))
      (node (ref "U1") (pin "40") (pinfunction "GPIO28_ADC2_40") (pintype "bidirectional"))
    )
    (net (code "67") (name "unconnected-(BTN1-Pad1)") (class "Default")
      (node (ref "BTN1") (pin "1") (pinfunction "1_1") (pintype "unspecified"))
    )
    (net (code "68") (name "unconnected-(BTN1-Pad4)") (class "Default")
      (node (ref "BTN1") (pin "4") (pinfunction "4_4") (pintype "unspecified"))
    )
    (net (code "69") (name "unconnected-(BTN2-Pad1)") (class "Default")
      (node (ref "BTN2") (pin "1") (pinfunction "1_1") (pintype "unspecified"))
    )
    (net (code "70") (name "unconnected-(BTN2-Pad4)") (class "Default")
      (node (ref "BTN2") (pin "4") (pinfunction "4_4") (pintype "unspecified"))
    )
    (net (code "71") (name "unconnected-(BTN3-Pad1)") (class "Default")
      (node (ref "BTN3") (pin "1") (pinfunction "1_1") (pintype "unspecified"))
    )
    (net (code "72") (name "unconnected-(BTN3-Pad4)") (class "Default")
      (node (ref "BTN3") (pin "4") (pinfunction "4_4") (pintype "unspecified"))
    )
    (net (code "73") (name "unconnected-(U1-GPIO29_ADC3-Pad41)") (class "Default")
      (node (ref "U1") (pin "41") (pinfunction "GPIO29_ADC3_41") (pintype "bidirectional"))
    )
    (net (code "74") (name "unconnected-(U6-Pad1)") (class "Default")
      (node (ref "U6") (pin "1") (pinfunction "1_1") (pintype "unspecified"))
    )
    (net (code "75") (name "unconnected-(U6-Pad8)") (class "Default")
      (node (ref "U6") (pin "8") (pinfunction "8_8") (pintype "unspecified"))
    )
    (net (code "76") (name "unconnected-(U7-NC-Pad9)") (class "Default")
      (node (ref "U7") (pin "9") (pinfunction "NC_9") (pintype "unspecified"))
    )
    (net (code "77") (name "unconnected-(USBC-SBU1-PadA8)") (class "Default")
      (node (ref "USBC") (pin "A8") (pinfunction "SBU1_A8") (pintype "unspecified"))
    )
    (net (code "78") (name "unconnected-(USBC-SBU2-PadB8)") (class "Default")
      (node (ref "USBC") (pin "B8") (pinfunction "SBU2_B8") (pintype "unspecified"))
    )
  )
)
